# GIP-client.net
KiCad netlist of a schematic drawn in EAGLE
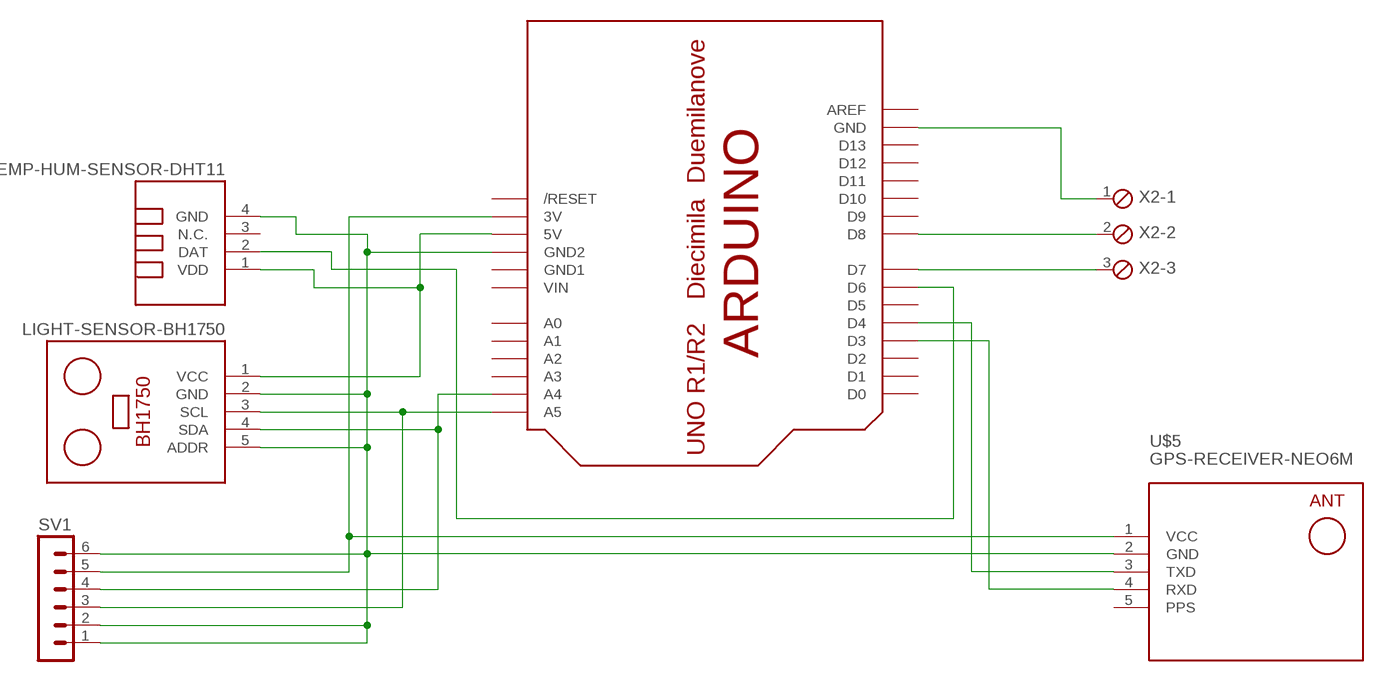
[diagram p0: schematic, sheet 1]

(export (version "E")
  (design (tool "Eeschema 10.0.6"))
  (components
    (comp (ref "SV1")
      (value "MA06-1")
      (footprint "eagle-import:MA06-1")
      (libsource (lib "eagle-import") (part "MA06-1"))
    )
    (comp (ref "U$2")
      (value "ARDUINO-BPLACE")
      (footprint "eagle-import:ARDUINO-BPLACE")
      (libsource (lib "eagle-import") (part "ARDUINO-BPLACE"))
    )
    (comp (ref "U$3")
      (value "TEMP-HUM-SENSOR-DHT11")
      (footprint "eagle-import:TEMP-HUM-SENSOR-DHT11")
      (libsource (lib "eagle-import") (part "TEMP-HUM-SENSOR-DHT11"))
    )
    (comp (ref "U$4")
      (value "LIGHT-SENSOR-BH1750")
      (footprint "eagle-import:LIGHT-SENSOR-BH1750")
      (libsource (lib "eagle-import") (part "LIGHT-SENSOR-BH1750"))
    )
    (comp (ref "U$5")
      (value "GPS-RECEIVER-NEO6M")
      (footprint "eagle-import:GPS-RECEIVER-NEO6M")
      (libsource (lib "eagle-import") (part "GPS-RECEIVER-NEO6M"))
    )
    (comp (ref "X2")
      (value "MPT3")
      (footprint "eagle-import:3POL254")
      (libsource (lib "eagle-import") (part "MPT3"))
    )
  )
  (nets
    (net (code "1") (name "/GND1") (class "Default")
      (node (ref "U$2") (pin "GND1") (pinfunction "GND1_GND1") (pintype "power_in"))
    )
    (net (code "2") (name "/PPS") (class "Default")
      (node (ref "U$5") (pin "5") (pinfunction "PPS_5") (pintype "power_in"))
    )
    (net (code "3") (name "/VIN") (class "Default")
      (node (ref "U$2") (pin "VIN") (pinfunction "VIN_VIN") (pintype "power_in"))
    )
    (net (code "4") (name "Net-(U$2-PadGND)") (class "Default")
      (node (ref "U$2") (pin "GND") (pinfunction "GND_GND") (pintype "power_in"))
      (node (ref "X2") (pin "1") (pinfunction "1_1") (pintype "passive"))
    )
    (net (code "5") (name "Net-(U$3-DAT)") (class "Default")
      (node (ref "U$2") (pin "D6") (pinfunction "D6_D6") (pintype "bidirectional"))
      (node (ref "U$3") (pin "2") (pinfunction "DAT_2") (pintype "bidirectional"))
    )
    (net (code "6") (name "Net-(U$3-GND)") (class "Default")
      (node (ref "SV1") (pin "1") (pinfunction "1_1") (pintype "passive"))
      (node (ref "SV1") (pin "2") (pinfunction "2_2") (pintype "passive"))
      (node (ref "SV1") (pin "6") (pinfunction "6_6") (pintype "passive"))
      (node (ref "U$2") (pin "GND2") (pinfunction "GND2_GND2") (pintype "power_in"))
      (node (ref "U$3") (pin "4") (pinfunction "GND_4") (pintype "power_in"))
      (node (ref "U$4") (pin "2") (pinfunction "GND_2") (pintype "power_in"))
      (node (ref "U$4") (pin "5") (pinfunction "ADDR_5") (pintype "bidirectional"))
      (node (ref "U$5") (pin "2") (pinfunction "GND_2") (pintype "bidirectional"))
    )
    (net (code "7") (name "Net-(U$3-VDD)") (class "Default")
      (node (ref "U$2") (pin "5V") (pinfunction "5V_5V") (pintype "power_in"))
      (node (ref "U$3") (pin "1") (pinfunction "VDD_1") (pintype "power_in"))
      (node (ref "U$4") (pin "1") (pinfunction "VCC_1") (pintype "power_in"))
    )
    (net (code "8") (name "Net-(U$4-SCL)") (class "Default")
      (node (ref "SV1") (pin "3") (pinfunction "3_3") (pintype "passive"))
      (node (ref "U$2") (pin "A5") (pinfunction "A5_A5") (pintype "bidirectional"))
      (node (ref "U$4") (pin "3") (pinfunction "SCL_3") (pintype "bidirectional"))
    )
    (net (code "9") (name "Net-(U$4-SDA)") (class "Default")
      (node (ref "SV1") (pin "4") (pinfunction "4_4") (pintype "passive"))
      (node (ref "U$2") (pin "A4") (pinfunction "A4_A4") (pintype "bidirectional"))
      (node (ref "U$4") (pin "4") (pinfunction "SDA_4") (pintype "bidirectional"))
    )
    (net (code "10") (name "Net-(U$5-RXD)") (class "Default")
      (node (ref "U$2") (pin "D3") (pinfunction "D3_D3") (pintype "bidirectional"))
      (node (ref "U$5") (pin "4") (pinfunction "RXD_4") (pintype "power_in"))
    )
    (net (code "11") (name "Net-(U$5-TXD)") (class "Default")
      (node (ref "U$2") (pin "D4") (pinfunction "D4_D4") (pintype "bidirectional"))
      (node (ref "U$5") (pin "3") (pinfunction "TXD_3") (pintype "bidirectional"))
    )
    (net (code "12") (name "Net-(U$5-VCC)") (class "Default")
      (node (ref "SV1") (pin "5") (pinfunction "5_5") (pintype "passive"))
      (node (ref "U$2") (pin "3V") (pinfunction "3V_3V") (pintype "power_in"))
      (node (ref "U$5") (pin "1") (pinfunction "VCC_1") (pintype "bidirectional"))
    )
    (net (code "13") (name "Net-(X2B-1)") (class "Default")
      (node (ref "U$2") (pin "D8") (pinfunction "D8_D8") (pintype "bidirectional"))
      (node (ref "X2") (pin "2") (pinfunction "1_2") (pintype "passive"))
    )
    (net (code "14") (name "Net-(X2C-1)") (class "Default")
      (node (ref "U$2") (pin "D7") (pinfunction "D7_D7") (pintype "bidirectional"))
      (node (ref "X2") (pin "3") (pinfunction "1_3") (pintype "passive"))
    )
    (net (code "15") (name "unconnected-(U$2-PadA0)") (class "Default")
      (node (ref "U$2") (pin "A0") (pinfunction "A0_A0") (pintype "bidirectional"))
    )
    (net (code "16") (name "unconnected-(U$2-PadA1)") (class "Default")
      (node (ref "U$2") (pin "A1") (pinfunction "A1_A1") (pintype "bidirectional"))
    )
    (net (code "17") (name "unconnected-(U$2-PadA2)") (class "Default")
      (node (ref "U$2") (pin "A2") (pinfunction "A2_A2") (pintype "bidirectional"))
    )
    (net (code "18") (name "unconnected-(U$2-PadA3)") (class "Default")
      (node (ref "U$2") (pin "A3") (pinfunction "A3_A3") (pintype "bidirectional"))
    )
    (net (code "19") (name "unconnected-(U$2-PadAREF)") (class "Default")
      (node (ref "U$2") (pin "AREF") (pinfunction "AREF_AREF") (pintype "bidirectional"))
    )
    (net (code "20") (name "unconnected-(U$2-PadD0)") (class "Default")
      (node (ref "U$2") (pin "D0") (pinfunction "D0_D0") (pintype "bidirectional"))
    )
    (net (code "21") (name "unconnected-(U$2-PadD1)") (class "Default")
      (node (ref "U$2") (pin "D1") (pinfunction "D1_D1") (pintype "bidirectional"))
    )
    (net (code "22") (name "unconnected-(U$2-PadD2)") (class "Default")
      (node (ref "U$2") (pin "D2") (pinfunction "D2_D2") (pintype "bidirectional"))
    )
    (net (code "23") (name "unconnected-(U$2-PadD5)") (class "Default")
      (node (ref "U$2") (pin "D5") (pinfunction "D5_D5") (pintype "bidirectional"))
    )
    (net (code "24") (name "unconnected-(U$2-PadD9)") (class "Default")
      (node (ref "U$2") (pin "D9") (pinfunction "D9_D9") (pintype "bidirectional"))
    )
    (net (code "25") (name "unconnected-(U$2-PadD10)") (class "Default")
      (node (ref "U$2") (pin "D10") (pinfunction "D10_D10") (pintype "bidirectional"))
    )
    (net (code "26") (name "unconnected-(U$2-PadD11)") (class "Default")
      (node (ref "U$2") (pin "D11") (pinfunction "D11_D11") (pintype "bidirectional"))
    )
    (net (code "27") (name "unconnected-(U$2-PadD12)") (class "Default")
      (node (ref "U$2") (pin "D12") (pinfunction "D12_D12") (pintype "bidirectional"))
    )
    (net (code "28") (name "unconnected-(U$2-PadD13)") (class "Default")
      (node (ref "U$2") (pin "D13") (pinfunction "D13_D13") (pintype "bidirectional"))
    )
    (net (code "29") (name "unconnected-(U$2-{slash}RESET-PadRESET)") (class "Default")
      (node (ref "U$2") (pin "RESET") (pinfunction "/RESET_RESET") (pintype "bidirectional"))
    )
    (net (code "30") (name "unconnected-(U$3-N.C.-Pad3)") (class "Default")
      (node (ref "U$3") (pin "3") (pinfunction "N.C._3") (pintype "passive"))
    )
  )
)
